# ROM-el_HN61256.net
KiCad netlist of a schematic drawn in EAGLE
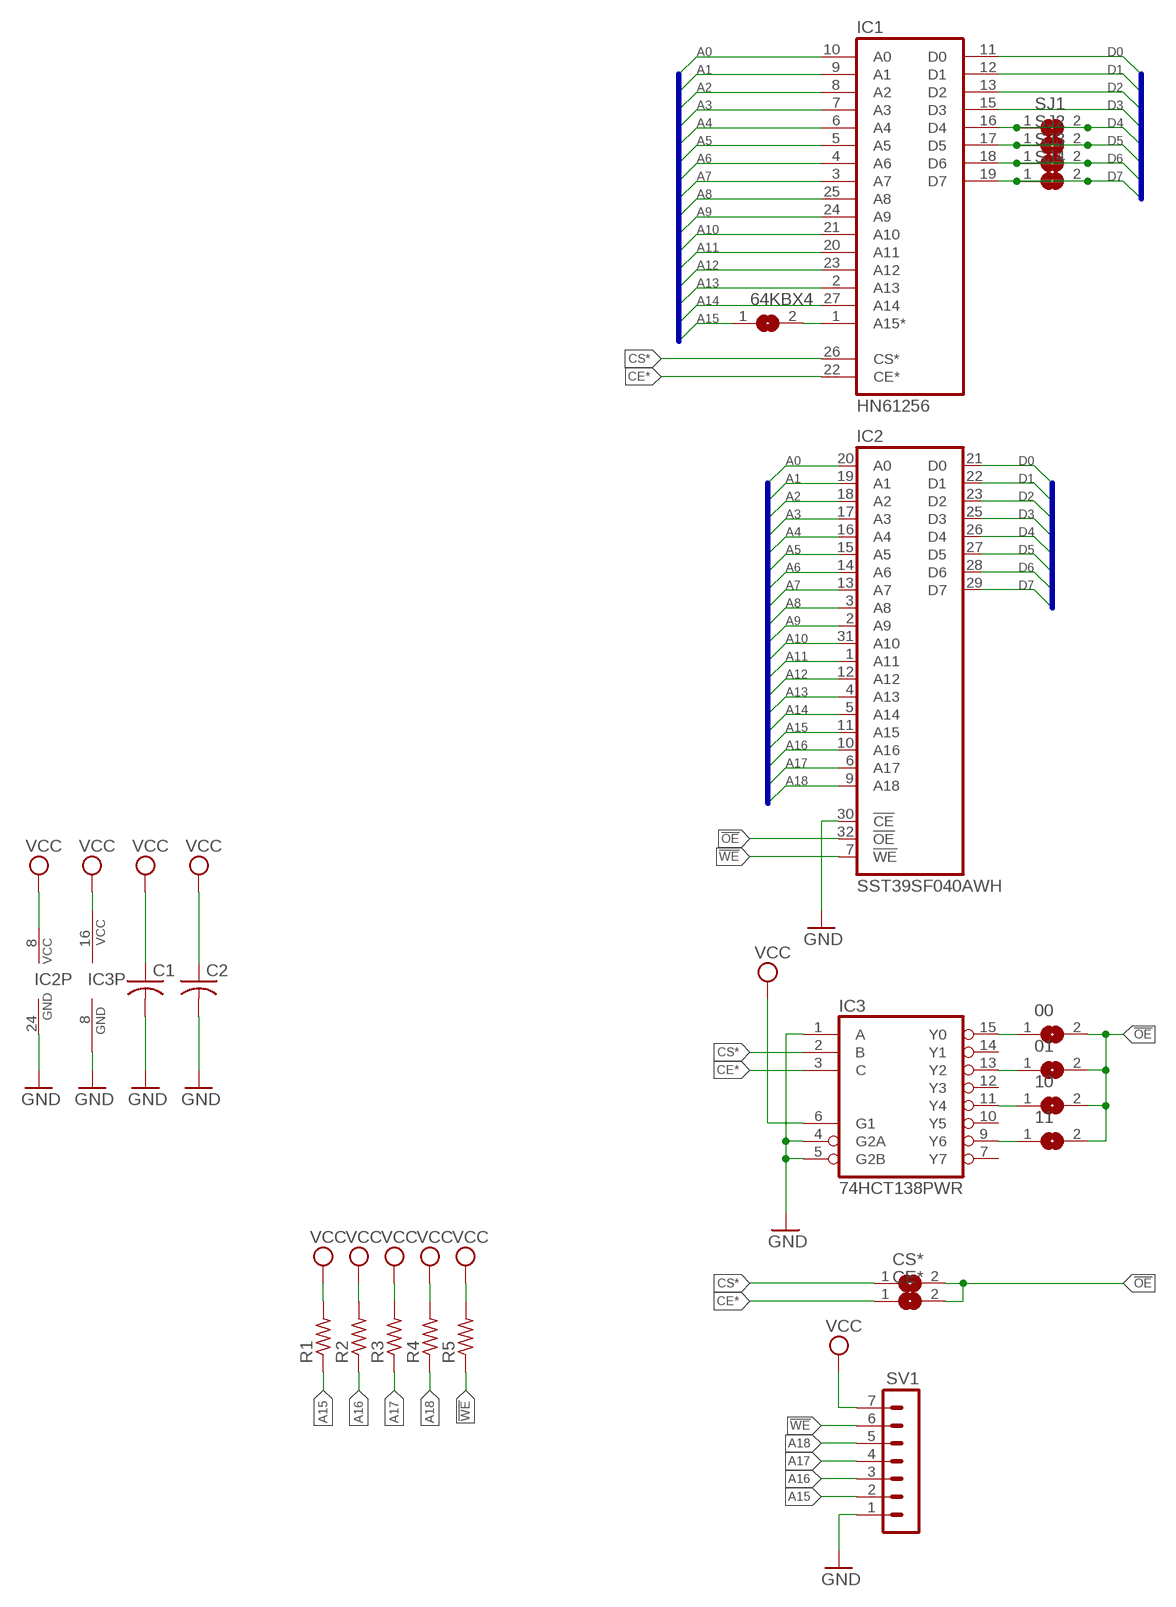
[diagram p0: schematic, sheet 1]

(export (version "E")
  (design (tool "Eeschema 10.0.6"))
  (components
    (comp (ref "00") (value "SJ") (footprint "eagle-import:SJ") (libsource (lib "eagle-import") (part "SJ")))
    (comp (ref "01") (value "SJ") (footprint "eagle-import:SJ") (libsource (lib "eagle-import") (part "SJ")))
    (comp (ref "10") (value "SJ") (footprint "eagle-import:SJ") (libsource (lib "eagle-import") (part "SJ")))
    (comp (ref "11") (value "SJ") (footprint "eagle-import:SJ") (libsource (lib "eagle-import") (part "SJ")))
    (comp (ref "64KBX4")
      (value "SJ")
      (footprint "eagle-import:SJ")
      (libsource (lib "eagle-import") (part "SJ"))
    )
    (comp (ref "C1")
      (value "C-USC0402")
      (footprint "eagle-import:C0402")
      (libsource (lib "eagle-import") (part "C-USC0402"))
    )
    (comp (ref "C2")
      (value "C-USC0402")
      (footprint "eagle-import:C0402")
      (libsource (lib "eagle-import") (part "C-USC0402"))
    )
    (comp (ref "CE*") (value "SJ") (footprint "eagle-import:SJ") (libsource (lib "eagle-import") (part "SJ")))
    (comp (ref "CS*") (value "SJ") (footprint "eagle-import:SJ") (libsource (lib "eagle-import") (part "SJ")))
    (comp (ref "IC1")
      (value "HN61256")
      (footprint "eagle-import:DIL28-6")
      (libsource (lib "eagle-import") (part "HN61256"))
    )
    (comp (ref "IC2")
      (value "SST39SF040AWH")
      (footprint "eagle-import:VSOP32")
      (libsource (lib "eagle-import") (part "SST39SF040AWH"))
    )
    (comp (ref "IC3")
      (value "74HCT138PWR")
      (footprint "eagle-import:TSSOP16")
      (libsource (lib "eagle-import") (part "74138PWRHCT"))
    )
    (comp (ref "R1")
      (value "R-US_R0402")
      (footprint "eagle-import:R0402")
      (libsource (lib "eagle-import") (part "R-US_R0402"))
    )
    (comp (ref "R2")
      (value "R-US_R0402")
      (footprint "eagle-import:R0402")
      (libsource (lib "eagle-import") (part "R-US_R0402"))
    )
    (comp (ref "R3")
      (value "R-US_R0402")
      (footprint "eagle-import:R0402")
      (libsource (lib "eagle-import") (part "R-US_R0402"))
    )
    (comp (ref "R4")
      (value "R-US_R0402")
      (footprint "eagle-import:R0402")
      (libsource (lib "eagle-import") (part "R-US_R0402"))
    )
    (comp (ref "R5")
      (value "R-US_R0402")
      (footprint "eagle-import:R0402")
      (libsource (lib "eagle-import") (part "R-US_R0402"))
    )
    (comp (ref "SJ1") (value "SJ") (footprint "eagle-import:SJ") (libsource (lib "eagle-import") (part "SJ")))
    (comp (ref "SJ2") (value "SJ") (footprint "eagle-import:SJ") (libsource (lib "eagle-import") (part "SJ")))
    (comp (ref "SJ3") (value "SJ") (footprint "eagle-import:SJ") (libsource (lib "eagle-import") (part "SJ")))
    (comp (ref "SJ4") (value "SJ") (footprint "eagle-import:SJ") (libsource (lib "eagle-import") (part "SJ")))
    (comp (ref "SV1")
      (value "MA07-1")
      (footprint "eagle-import:MA07-1")
      (libsource (lib "eagle-import") (part "MA07-1"))
    )
  )
  (nets
    (net (code "1") (name "/A0") (class "Default")
      (node (ref "IC1") (pin "10") (pinfunction "A0_10") (pintype "input"))
      (node (ref "IC2") (pin "20") (pinfunction "A0_20") (pintype "input"))
    )
    (net (code "2") (name "/A1") (class "Default")
      (node (ref "IC1") (pin "9") (pinfunction "A1_9") (pintype "input"))
      (node (ref "IC2") (pin "19") (pinfunction "A1_19") (pintype "input"))
    )
    (net (code "3") (name "/A2") (class "Default")
      (node (ref "IC1") (pin "8") (pinfunction "A2_8") (pintype "input"))
      (node (ref "IC2") (pin "18") (pinfunction "A2_18") (pintype "input"))
    )
    (net (code "4") (name "/A3") (class "Default")
      (node (ref "IC1") (pin "7") (pinfunction "A3_7") (pintype "input"))
      (node (ref "IC2") (pin "17") (pinfunction "A3_17") (pintype "input"))
    )
    (net (code "5") (name "/A4") (class "Default")
      (node (ref "IC1") (pin "6") (pinfunction "A4_6") (pintype "input"))
      (node (ref "IC2") (pin "16") (pinfunction "A4_16") (pintype "input"))
    )
    (net (code "6") (name "/A5") (class "Default")
      (node (ref "IC1") (pin "5") (pinfunction "A5_5") (pintype "input"))
      (node (ref "IC2") (pin "15") (pinfunction "A5_15") (pintype "input"))
    )
    (net (code "7") (name "/A6") (class "Default")
      (node (ref "IC1") (pin "4") (pinfunction "A6_4") (pintype "input"))
      (node (ref "IC2") (pin "14") (pinfunction "A6_14") (pintype "input"))
    )
    (net (code "8") (name "/A7") (class "Default")
      (node (ref "IC1") (pin "3") (pinfunction "A7_3") (pintype "input"))
      (node (ref "IC2") (pin "13") (pinfunction "A7_13") (pintype "input"))
    )
    (net (code "9") (name "/A8") (class "Default")
      (node (ref "IC1") (pin "25") (pinfunction "A8_25") (pintype "input"))
      (node (ref "IC2") (pin "3") (pinfunction "A8_3") (pintype "input"))
    )
    (net (code "10") (name "/A9") (class "Default")
      (node (ref "IC1") (pin "24") (pinfunction "A9_24") (pintype "input"))
      (node (ref "IC2") (pin "2") (pinfunction "A9_2") (pintype "input"))
    )
    (net (code "11") (name "/A10") (class "Default")
      (node (ref "IC1") (pin "21") (pinfunction "A10_21") (pintype "input"))
      (node (ref "IC2") (pin "31") (pinfunction "A10_31") (pintype "input"))
    )
    (net (code "12") (name "/A11") (class "Default")
      (node (ref "IC1") (pin "20") (pinfunction "A11_20") (pintype "input"))
      (node (ref "IC2") (pin "1") (pinfunction "A11_1") (pintype "input"))
    )
    (net (code "13") (name "/A12") (class "Default")
      (node (ref "IC1") (pin "23") (pinfunction "A12_23") (pintype "input"))
      (node (ref "IC2") (pin "12") (pinfunction "A12_12") (pintype "input"))
    )
    (net (code "14") (name "/A13") (class "Default")
      (node (ref "IC1") (pin "2") (pinfunction "A13_2") (pintype "input"))
      (node (ref "IC2") (pin "4") (pinfunction "A13_4") (pintype "input"))
    )
    (net (code "15") (name "/A14") (class "Default")
      (node (ref "IC1") (pin "27") (pinfunction "A14_27") (pintype "input"))
      (node (ref "IC2") (pin "5") (pinfunction "A14_5") (pintype "input"))
    )
    (net (code "16") (name "/D0") (class "Default")
      (node (ref "IC1") (pin "11") (pinfunction "D0_11") (pintype "bidirectional"))
      (node (ref "IC2") (pin "21") (pinfunction "D0_21") (pintype "bidirectional"))
    )
    (net (code "17") (name "/D1") (class "Default")
      (node (ref "IC1") (pin "12") (pinfunction "D1_12") (pintype "bidirectional"))
      (node (ref "IC2") (pin "22") (pinfunction "D1_22") (pintype "bidirectional"))
    )
    (net (code "18") (name "/D2") (class "Default")
      (node (ref "IC1") (pin "13") (pinfunction "D2_13") (pintype "bidirectional"))
      (node (ref "IC2") (pin "23") (pinfunction "D2_23") (pintype "bidirectional"))
    )
    (net (code "19") (name "/D3") (class "Default")
      (node (ref "IC1") (pin "15") (pinfunction "D3_15") (pintype "bidirectional"))
      (node (ref "IC2") (pin "25") (pinfunction "D3_25") (pintype "bidirectional"))
    )
    (net (code "20") (name "/D4") (class "Default")
      (node (ref "IC1") (pin "16") (pinfunction "D4_16") (pintype "bidirectional"))
      (node (ref "IC2") (pin "26") (pinfunction "D4_26") (pintype "bidirectional"))
      (node (ref "SJ1") (pin "1") (pinfunction "1_1") (pintype "passive"))
      (node (ref "SJ1") (pin "2") (pinfunction "2_2") (pintype "passive"))
    )
    (net (code "21") (name "/D5") (class "Default")
      (node (ref "IC1") (pin "17") (pinfunction "D5_17") (pintype "bidirectional"))
      (node (ref "IC2") (pin "27") (pinfunction "D5_27") (pintype "bidirectional"))
      (node (ref "SJ2") (pin "1") (pinfunction "1_1") (pintype "passive"))
      (node (ref "SJ2") (pin "2") (pinfunction "2_2") (pintype "passive"))
    )
    (net (code "22") (name "/D6") (class "Default")
      (node (ref "IC1") (pin "18") (pinfunction "D6_18") (pintype "bidirectional"))
      (node (ref "IC2") (pin "28") (pinfunction "D6_28") (pintype "bidirectional"))
      (node (ref "SJ3") (pin "1") (pinfunction "1_1") (pintype "passive"))
      (node (ref "SJ3") (pin "2") (pinfunction "2_2") (pintype "passive"))
    )
    (net (code "23") (name "/D7") (class "Default")
      (node (ref "IC1") (pin "19") (pinfunction "D7_19") (pintype "bidirectional"))
      (node (ref "IC2") (pin "29") (pinfunction "D7_29") (pintype "bidirectional"))
      (node (ref "SJ4") (pin "1") (pinfunction "1_1") (pintype "passive"))
      (node (ref "SJ4") (pin "2") (pinfunction "2_2") (pintype "passive"))
    )
    (net (code "24") (name "/~{OE}") (class "Default")
      (node (ref "00") (pin "2") (pinfunction "2_2") (pintype "passive"))
      (node (ref "01") (pin "2") (pinfunction "2_2") (pintype "passive"))
      (node (ref "10") (pin "2") (pinfunction "2_2") (pintype "passive"))
      (node (ref "11") (pin "2") (pinfunction "2_2") (pintype "passive"))
      (node (ref "CE*") (pin "2") (pinfunction "2_2") (pintype "passive"))
      (node (ref "CS*") (pin "2") (pinfunction "2_2") (pintype "passive"))
      (node (ref "IC2") (pin "32") (pinfunction "~{OE}_32") (pintype "input"))
    )
    (net (code "25") (name "/~{WE}") (class "Default")
      (node (ref "IC2") (pin "7") (pinfunction "~{WE}_7") (pintype "input"))
      (node (ref "R5") (pin "1") (pinfunction "1_1") (pintype "passive"))
      (node (ref "SV1") (pin "6") (pinfunction "6_6") (pintype "passive"))
    )
    (net (code "26") (name "A15") (class "Default")
      (node (ref "64KBX4") (pin "1") (pinfunction "1_1") (pintype "passive"))
      (node (ref "IC2") (pin "11") (pinfunction "A15_11") (pintype "input"))
      (node (ref "R1") (pin "1") (pinfunction "1_1") (pintype "passive"))
      (node (ref "SV1") (pin "2") (pinfunction "2_2") (pintype "passive"))
    )
    (net (code "27") (name "A16") (class "Default")
      (node (ref "IC2") (pin "10") (pinfunction "A16_10") (pintype "input"))
      (node (ref "R2") (pin "1") (pinfunction "1_1") (pintype "passive"))
      (node (ref "SV1") (pin "3") (pinfunction "3_3") (pintype "passive"))
    )
    (net (code "28") (name "A17") (class "Default")
      (node (ref "IC2") (pin "6") (pinfunction "A17_6") (pintype "input"))
      (node (ref "R3") (pin "1") (pinfunction "1_1") (pintype "passive"))
      (node (ref "SV1") (pin "4") (pinfunction "4_4") (pintype "passive"))
    )
    (net (code "29") (name "A18") (class "Default")
      (node (ref "IC2") (pin "9") (pinfunction "A18_9") (pintype "input"))
      (node (ref "R4") (pin "1") (pinfunction "1_1") (pintype "passive"))
      (node (ref "SV1") (pin "5") (pinfunction "5_5") (pintype "passive"))
    )
    (net (code "30") (name "CE*") (class "Default")
      (node (ref "CE*") (pin "1") (pinfunction "1_1") (pintype "passive"))
      (node (ref "IC1") (pin "22") (pinfunction "CE*_22") (pintype "input"))
      (node (ref "IC3") (pin "3") (pinfunction "C_3") (pintype "input"))
    )
    (net (code "31") (name "CS*") (class "Default")
      (node (ref "CS*") (pin "1") (pinfunction "1_1") (pintype "passive"))
      (node (ref "IC1") (pin "26") (pinfunction "CS*_26") (pintype "input"))
      (node (ref "IC3") (pin "2") (pinfunction "B_2") (pintype "input"))
    )
    (net (code "32") (name "GND") (class "Default")
      (node (ref "C1") (pin "2") (pinfunction "2_2") (pintype "passive"))
      (node (ref "C2") (pin "2") (pinfunction "2_2") (pintype "passive"))
      (node (ref "IC2") (pin "24") (pinfunction "GND_24") (pintype "power_in"))
      (node (ref "IC2") (pin "30") (pinfunction "~{CE}_30") (pintype "input"))
      (node (ref "IC3") (pin "1") (pinfunction "A_1") (pintype "input"))
      (node (ref "IC3") (pin "4") (pinfunction "G2A_4") (pintype "input"))
      (node (ref "IC3") (pin "5") (pinfunction "G2B_5") (pintype "input"))
      (node (ref "IC3") (pin "8") (pinfunction "GND_8") (pintype "power_in"))
      (node (ref "SV1") (pin "1") (pinfunction "1_1") (pintype "passive"))
    )
    (net (code "33") (name "Net-(IC1A-A15*)") (class "Default")
      (node (ref "64KBX4") (pin "2") (pinfunction "2_2") (pintype "passive"))
      (node (ref "IC1") (pin "1") (pinfunction "A15*_1") (pintype "input"))
    )
    (net (code "34") (name "Net-(IC3A-Y0)") (class "Default")
      (node (ref "00") (pin "1") (pinfunction "1_1") (pintype "passive"))
      (node (ref "IC3") (pin "15") (pinfunction "Y0_15") (pintype "output"))
    )
    (net (code "35") (name "Net-(IC3A-Y2)") (class "Default")
      (node (ref "01") (pin "1") (pinfunction "1_1") (pintype "passive"))
      (node (ref "IC3") (pin "13") (pinfunction "Y2_13") (pintype "output"))
    )
    (net (code "36") (name "Net-(IC3A-Y4)") (class "Default")
      (node (ref "10") (pin "1") (pinfunction "1_1") (pintype "passive"))
      (node (ref "IC3") (pin "11") (pinfunction "Y4_11") (pintype "output"))
    )
    (net (code "37") (name "Net-(IC3A-Y6)") (class "Default")
      (node (ref "11") (pin "1") (pinfunction "1_1") (pintype "passive"))
      (node (ref "IC3") (pin "9") (pinfunction "Y6_9") (pintype "output"))
    )
    (net (code "38") (name "VCC") (class "Default")
      (node (ref "C1") (pin "1") (pinfunction "1_1") (pintype "passive"))
      (node (ref "C2") (pin "1") (pinfunction "1_1") (pintype "passive"))
      (node (ref "IC2") (pin "8") (pinfunction "VCC_8") (pintype "power_in"))
      (node (ref "IC3") (pin "16") (pinfunction "VCC_16") (pintype "power_in"))
      (node (ref "IC3") (pin "6") (pinfunction "G1_6") (pintype "input"))
      (node (ref "R1") (pin "2") (pinfunction "2_2") (pintype "passive"))
      (node (ref "R2") (pin "2") (pinfunction "2_2") (pintype "passive"))
      (node (ref "R3") (pin "2") (pinfunction "2_2") (pintype "passive"))
      (node (ref "R4") (pin "2") (pinfunction "2_2") (pintype "passive"))
      (node (ref "R5") (pin "2") (pinfunction "2_2") (pintype "passive"))
      (node (ref "SV1") (pin "7") (pinfunction "7_7") (pintype "passive"))
    )
    (net (code "39") (name "unconnected-(IC3A-Y1-Pad14)") (class "Default")
      (node (ref "IC3") (pin "14") (pinfunction "Y1_14") (pintype "output"))
    )
    (net (code "40") (name "unconnected-(IC3A-Y3-Pad12)") (class "Default")
      (node (ref "IC3") (pin "12") (pinfunction "Y3_12") (pintype "output"))
    )
    (net (code "41") (name "unconnected-(IC3A-Y5-Pad10)") (class "Default")
      (node (ref "IC3") (pin "10") (pinfunction "Y5_10") (pintype "output"))
    )
    (net (code "42") (name "unconnected-(IC3A-Y7-Pad7)") (class "Default")
      (node (ref "IC3") (pin "7") (pinfunction "Y7_7") (pintype "output"))
    )
  )
)
